# prelab_semaine2.net
KiCad netlist of a schematic drawn in Altium Designer
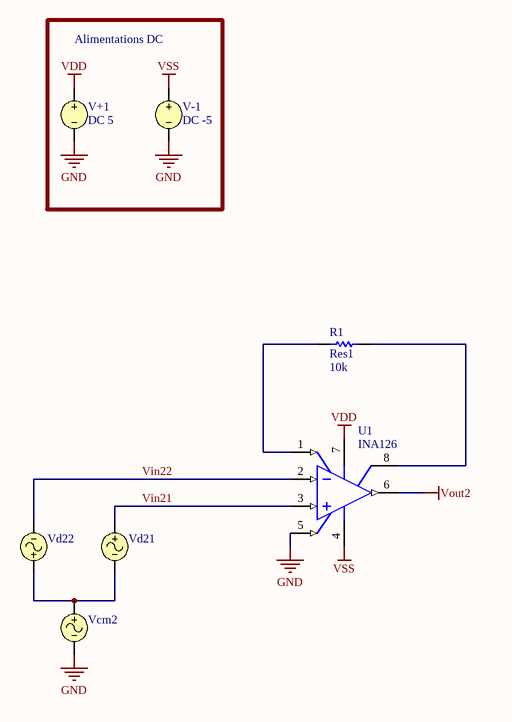
[diagram p0: prelab_semaine2.SchDoc]

(export (version "E")
  (design (tool "Eeschema 10.0.6"))
  (components
    (comp (ref "R1")
      (value "Res1")
      (footprint "AXIAL-0.3")
      (description "Resistor")
      (fields (field (name "ALTIUM_VALUE") "10k") (field (name "PUBLISHER") "Altium Limited"))
      (libsource (lib "Miscellaneous Devices") (part "Res1"))
    )
    (comp (ref "U1")
      (value "INA126")
      (description "Micropower Instrumentation Amplifier")
      (fields (field (name "PUBLISHER") "Altium Limited"))
      (libsource (lib "G3Lib3") (part "INA126"))
    )
    (comp (ref "V+1")
      (value "DC 5")
      (description "Voltage Source")
      (fields (field (name "PUBLISHER") "Altium Limited"))
      (libsource (lib "Simulation Sources") (part "VSRC"))
    )
    (comp (ref "V-1")
      (value "DC -5")
      (description "Voltage Source")
      (fields (field (name "PUBLISHER") "Altium Limited"))
      (libsource (lib "Simulation Sources") (part "VSRC"))
    )
    (comp (ref "Vcm2")
      (value "SIN(0 150m 120 0 0 0)")
      (description "Sinusoidal Voltage Source")
      (fields (field (name "PUBLISHER") "Altium Limited"))
      (libsource (lib "Simulation Sources") (part "VSIN"))
    )
    (comp (ref "Vd21")
      (value "SIN(0 0 2k 0 0 0)")
      (description "Sinusoidal Voltage Source")
      (fields (field (name "PUBLISHER") "Altium Limited"))
      (libsource (lib "Simulation Sources") (part "VSIN"))
    )
    (comp (ref "Vd22")
      (value "SIN(0 0 2k 0 0 0)")
      (description "Sinusoidal Voltage Source")
      (fields (field (name "PUBLISHER") "Altium Limited"))
      (libsource (lib "Simulation Sources") (part "VSIN"))
    )
  )
  (nets
    (net (code "1") (name "/Vin21") (class "Default")
      (node (ref "U1") (pin "3") (pinfunction "IN+_3") (pintype "input"))
      (node (ref "Vd21") (pin "1") (pinfunction "1_1") (pintype "passive"))
    )
    (net (code "2") (name "/Vin22") (class "Default")
      (node (ref "U1") (pin "2") (pinfunction "IN-_2") (pintype "input"))
      (node (ref "Vd22") (pin "2") (pinfunction "2_2") (pintype "passive"))
    )
    (net (code "3") (name "GND") (class "Default")
      (node (ref "U1") (pin "5") (pinfunction "REFA_5") (pintype "input"))
      (node (ref "V+1") (pin "2") (pinfunction "2_2") (pintype "passive"))
      (node (ref "V-1") (pin "2") (pinfunction "2_2") (pintype "passive"))
      (node (ref "Vcm2") (pin "2") (pinfunction "2_2") (pintype "passive"))
    )
    (net (code "4") (name "Net-(U1-COMP)") (class "Default")
      (node (ref "R1") (pin "2") (pinfunction "2_2") (pintype "passive"))
      (node (ref "U1") (pin "8") (pinfunction "COMP_8") (pintype "passive"))
    )
    (net (code "5") (name "Net-(U1-REFB)") (class "Default")
      (node (ref "R1") (pin "1") (pinfunction "1_1") (pintype "passive"))
      (node (ref "U1") (pin "1") (pinfunction "REFB_1") (pintype "input"))
    )
    (net (code "6") (name "Net-(Vcm2-Pad1)") (class "Default")
      (node (ref "Vcm2") (pin "1") (pinfunction "1_1") (pintype "passive"))
      (node (ref "Vd21") (pin "2") (pinfunction "2_2") (pintype "passive"))
      (node (ref "Vd22") (pin "1") (pinfunction "1_1") (pintype "passive"))
    )
    (net (code "7") (name "VDD") (class "Default")
      (node (ref "U1") (pin "7") (pinfunction "V+_7") (pintype "power_in"))
      (node (ref "V+1") (pin "1") (pinfunction "1_1") (pintype "passive"))
    )
    (net (code "8") (name "VSS") (class "Default")
      (node (ref "U1") (pin "4") (pinfunction "V-_4") (pintype "power_in"))
      (node (ref "V-1") (pin "1") (pinfunction "1_1") (pintype "passive"))
    )
    (net (code "9") (name "Vout2") (class "Default")
      (node (ref "U1") (pin "6") (pinfunction "OUT_6") (pintype "output"))
    )
  )
)
